# Video_OUT.net
KiCad netlist of a schematic drawn in Altium Designer
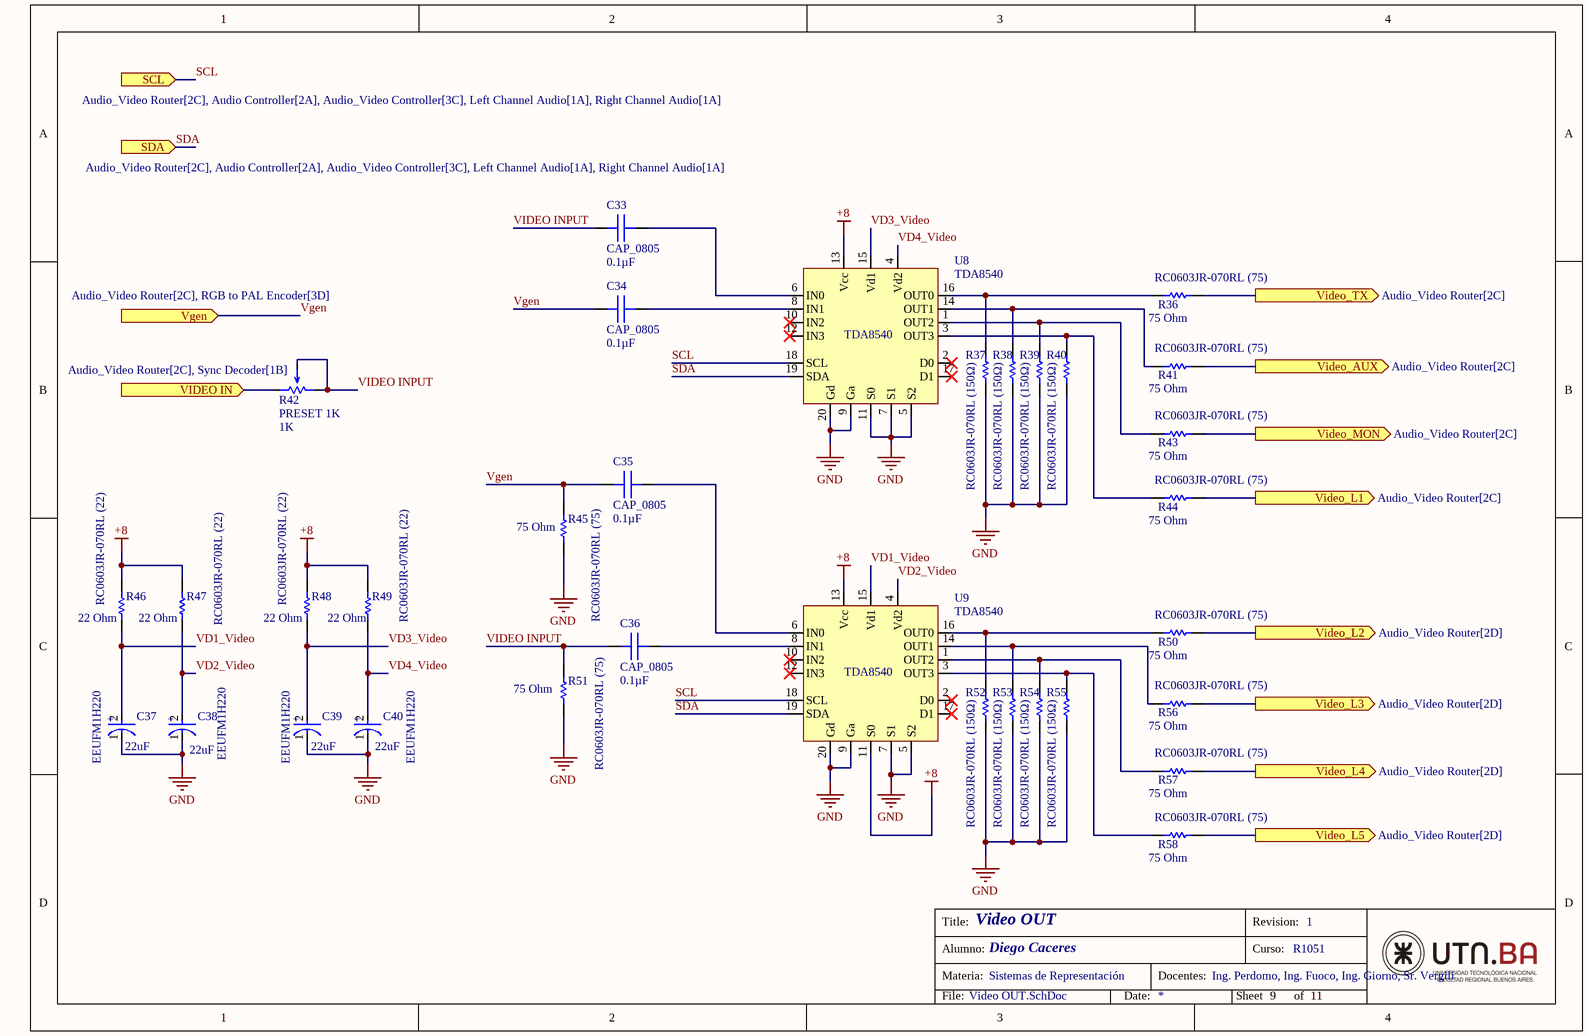
[diagram p0: Video OUT.SchDoc]

(export (version "E")
  (design (tool "Eeschema 10.0.6"))
  (components
    (comp (ref "C33")
      (value "CAP_0805")
      (footprint "0805_CAPACITOR_DCACERES")
      (description "Capacitor SMD, encapsulado 0805")
      (fields (field (name "ALTIUM_VALUE") "0.1µF"))
      (libsource (lib "PF_Schlib") (part "CAPACITOR_0805_Caceres"))
    )
    (comp (ref "C34")
      (value "CAP_0805")
      (footprint "0805_CAPACITOR_DCACERES")
      (description "Capacitor SMD, encapsulado 0805")
      (fields (field (name "ALTIUM_VALUE") "0.1µF"))
      (libsource (lib "PF_Schlib") (part "CAPACITOR_0805_Caceres"))
    )
    (comp (ref "C35")
      (value "CAP_0805")
      (footprint "0805_CAPACITOR_DCACERES")
      (description "Capacitor SMD, encapsulado 0805")
      (fields (field (name "ALTIUM_VALUE") "0.1µF"))
      (libsource (lib "PF_Schlib") (part "CAPACITOR_0805_Caceres"))
    )
    (comp (ref "C36")
      (value "CAP_0805")
      (footprint "0805_CAPACITOR_DCACERES")
      (description "Capacitor SMD, encapsulado 0805")
      (fields (field (name "ALTIUM_VALUE") "0.1µF"))
      (libsource (lib "PF_Schlib") (part "CAPACITOR_0805_Caceres"))
    )
    (comp (ref "C37")
      (value "EEUFM1H220")
      (footprint "FP-RAD-TH-D_5_0_5-L_11_1-MFG")
      (description "Aluminum Electrolytic Capacitors (Radial Lead Type) 22uF ±20% 50V")
      (fields
        (field (name "TOLERANCE") "20%")
        (field (name "VOLTAGE") "50V")
        (field (name "CAPACITANCE") "22uF")
      )
      (libsource (lib "Altium Content Vault") (part "a00bbbee19879c290e62620ae7e47b1"))
    )
    (comp (ref "C38")
      (value "EEUFM1H220")
      (footprint "FP-RAD-TH-D_5_0_5-L_11_1-MFG")
      (description "Aluminum Electrolytic Capacitors (Radial Lead Type) 22uF ±20% 50V")
      (fields
        (field (name "TOLERANCE") "20%")
        (field (name "VOLTAGE") "50V")
        (field (name "CAPACITANCE") "22uF")
      )
      (libsource (lib "Altium Content Vault") (part "a00bbbee19879c290e62620ae7e47b1"))
    )
    (comp (ref "C39")
      (value "EEUFM1H220")
      (footprint "FP-RAD-TH-D_5_0_5-L_11_1-MFG")
      (description "Aluminum Electrolytic Capacitors (Radial Lead Type) 22uF ±20% 50V")
      (fields
        (field (name "TOLERANCE") "20%")
        (field (name "VOLTAGE") "50V")
        (field (name "CAPACITANCE") "22uF")
      )
      (libsource (lib "Altium Content Vault") (part "a00bbbee19879c290e62620ae7e47b1"))
    )
    (comp (ref "C40")
      (value "EEUFM1H220")
      (footprint "FP-RAD-TH-D_5_0_5-L_11_1-MFG")
      (description "Aluminum Electrolytic Capacitors (Radial Lead Type) 22uF ±20% 50V")
      (fields
        (field (name "TOLERANCE") "20%")
        (field (name "VOLTAGE") "50V")
        (field (name "CAPACITANCE") "22uF")
      )
      (libsource (lib "Altium Content Vault") (part "a00bbbee19879c290e62620ae7e47b1"))
    )
    (comp (ref "R36")
      (value "RC0603JR-070RL (75)")
      (footprint "RESC1608X55X25ML10T15")
      (description "Chip Resistor, 0 Ohm, +/- 5%, 0.1 W, -55 to 155 degC, 0603 (1608 Metric), RoHS, Tape and Reel")
      (fields
        (field (name "TOLERANCE") "5%")
        (field (name "RESISTANCE") "75 Ohm")
        (field (name "MANUFACTURER") "Yageo")
      )
      (libsource (lib "Altium Content Vault") (part "RES-2"))
    )
    (comp (ref "R37")
      (value "RC0603JR-070RL (150Ω)")
      (footprint "RESC1608X55X25ML10T15")
      (description "Chip Resistor, 0 Ohm, +/- 5%, 0.1 W, -55 to 155 degC, 0603 (1608 Metric), RoHS, Tape and Reel")
      (fields (field (name "TOLERANCE") "5%") (field (name "MANUFACTURER") "Yageo"))
      (libsource (lib "Altium Content Vault") (part "RES-2"))
    )
    (comp (ref "R38")
      (value "RC0603JR-070RL (150Ω)")
      (footprint "RESC1608X55X25ML10T15")
      (description "Chip Resistor, 0 Ohm, +/- 5%, 0.1 W, -55 to 155 degC, 0603 (1608 Metric), RoHS, Tape and Reel")
      (fields (field (name "TOLERANCE") "5%") (field (name "MANUFACTURER") "Yageo"))
      (libsource (lib "Altium Content Vault") (part "RES-2"))
    )
    (comp (ref "R39")
      (value "RC0603JR-070RL (150Ω)")
      (footprint "RESC1608X55X25ML10T15")
      (description "Chip Resistor, 0 Ohm, +/- 5%, 0.1 W, -55 to 155 degC, 0603 (1608 Metric), RoHS, Tape and Reel")
      (fields (field (name "TOLERANCE") "5%") (field (name "MANUFACTURER") "Yageo"))
      (libsource (lib "Altium Content Vault") (part "RES-2"))
    )
    (comp (ref "R40")
      (value "RC0603JR-070RL (150Ω)")
      (footprint "RESC1608X55X25ML10T15")
      (description "Chip Resistor, 0 Ohm, +/- 5%, 0.1 W, -55 to 155 degC, 0603 (1608 Metric), RoHS, Tape and Reel")
      (fields (field (name "TOLERANCE") "5%") (field (name "MANUFACTURER") "Yageo"))
      (libsource (lib "Altium Content Vault") (part "RES-2"))
    )
    (comp (ref "R41")
      (value "RC0603JR-070RL (75)")
      (footprint "RESC1608X55X25ML10T15")
      (description "Chip Resistor, 0 Ohm, +/- 5%, 0.1 W, -55 to 155 degC, 0603 (1608 Metric), RoHS, Tape and Reel")
      (fields
        (field (name "TOLERANCE") "5%")
        (field (name "RESISTANCE") "75 Ohm")
        (field (name "MANUFACTURER") "Yageo")
      )
      (libsource (lib "Altium Content Vault") (part "RES-2"))
    )
    (comp (ref "R42")
      (value "PRESET 1K")
      (footprint "3386P_PRESET_1K_DCaceres")
      (description "Preset 1k, Thru Hole\r\nManufacturer Part Search 3386P-1-472LF")
      (fields (field (name "ALTIUM_VALUE") "1K") (field (name "PARTNUMBER") "3386P-1-472LF"))
      (libsource (lib "PF_Schlib") (part "Preset_1K_Caceres"))
    )
    (comp (ref "R43")
      (value "RC0603JR-070RL (75)")
      (footprint "RESC1608X55X25ML10T15")
      (description "Chip Resistor, 0 Ohm, +/- 5%, 0.1 W, -55 to 155 degC, 0603 (1608 Metric), RoHS, Tape and Reel")
      (fields
        (field (name "TOLERANCE") "5%")
        (field (name "RESISTANCE") "75 Ohm")
        (field (name "MANUFACTURER") "Yageo")
      )
      (libsource (lib "Altium Content Vault") (part "RES-2"))
    )
    (comp (ref "R44")
      (value "RC0603JR-070RL (75)")
      (footprint "RESC1608X55X25ML10T15")
      (description "Chip Resistor, 0 Ohm, +/- 5%, 0.1 W, -55 to 155 degC, 0603 (1608 Metric), RoHS, Tape and Reel")
      (fields
        (field (name "TOLERANCE") "5%")
        (field (name "RESISTANCE") "75 Ohm")
        (field (name "MANUFACTURER") "Yageo")
      )
      (libsource (lib "Altium Content Vault") (part "RES-2"))
    )
    (comp (ref "R45")
      (value "RC0603JR-070RL (75)")
      (footprint "RESC1608X55X25ML10T15")
      (description "Chip Resistor, 0 Ohm, +/- 5%, 0.1 W, -55 to 155 degC, 0603 (1608 Metric), RoHS, Tape and Reel")
      (fields
        (field (name "TOLERANCE") "5%")
        (field (name "RESISTANCE") "75 Ohm")
        (field (name "MANUFACTURER") "Yageo")
      )
      (libsource (lib "Altium Content Vault") (part "RES-2"))
    )
    (comp (ref "R46")
      (value "RC0603JR-070RL (22)")
      (footprint "RESC1608X55X25ML10T15")
      (description "Chip Resistor, 0 Ohm, +/- 5%, 0.1 W, -55 to 155 degC, 0603 (1608 Metric), RoHS, Tape and Reel")
      (fields
        (field (name "TOLERANCE") "5%")
        (field (name "RESISTANCE") "22 Ohm")
        (field (name "MANUFACTURER") "Yageo")
      )
      (libsource (lib "Altium Content Vault") (part "RES-2"))
    )
    (comp (ref "R47")
      (value "RC0603JR-070RL (22)")
      (footprint "RESC1608X55X25ML10T15")
      (description "Chip Resistor, 0 Ohm, +/- 5%, 0.1 W, -55 to 155 degC, 0603 (1608 Metric), RoHS, Tape and Reel")
      (fields
        (field (name "TOLERANCE") "5%")
        (field (name "RESISTANCE") "22 Ohm")
        (field (name "MANUFACTURER") "Yageo")
      )
      (libsource (lib "Altium Content Vault") (part "RES-2"))
    )
    (comp (ref "R48")
      (value "RC0603JR-070RL (22)")
      (footprint "RESC1608X55X25ML10T15")
      (description "Chip Resistor, 0 Ohm, +/- 5%, 0.1 W, -55 to 155 degC, 0603 (1608 Metric), RoHS, Tape and Reel")
      (fields
        (field (name "TOLERANCE") "5%")
        (field (name "RESISTANCE") "22 Ohm")
        (field (name "MANUFACTURER") "Yageo")
      )
      (libsource (lib "Altium Content Vault") (part "RES-2"))
    )
    (comp (ref "R49")
      (value "RC0603JR-070RL (22)")
      (footprint "RESC1608X55X25ML10T15")
      (description "Chip Resistor, 0 Ohm, +/- 5%, 0.1 W, -55 to 155 degC, 0603 (1608 Metric), RoHS, Tape and Reel")
      (fields
        (field (name "TOLERANCE") "5%")
        (field (name "RESISTANCE") "22 Ohm")
        (field (name "MANUFACTURER") "Yageo")
      )
      (libsource (lib "Altium Content Vault") (part "RES-2"))
    )
    (comp (ref "R50")
      (value "RC0603JR-070RL (75)")
      (footprint "RESC1608X55X25ML10T15")
      (description "Chip Resistor, 0 Ohm, +/- 5%, 0.1 W, -55 to 155 degC, 0603 (1608 Metric), RoHS, Tape and Reel")
      (fields
        (field (name "TOLERANCE") "5%")
        (field (name "RESISTANCE") "75 Ohm")
        (field (name "MANUFACTURER") "Yageo")
      )
      (libsource (lib "Altium Content Vault") (part "RES-2"))
    )
    (comp (ref "R51")
      (value "RC0603JR-070RL (75)")
      (footprint "RESC1608X55X25ML10T15")
      (description "Chip Resistor, 0 Ohm, +/- 5%, 0.1 W, -55 to 155 degC, 0603 (1608 Metric), RoHS, Tape and Reel")
      (fields
        (field (name "TOLERANCE") "5%")
        (field (name "RESISTANCE") "75 Ohm")
        (field (name "MANUFACTURER") "Yageo")
      )
      (libsource (lib "Altium Content Vault") (part "RES-2"))
    )
    (comp (ref "R52")
      (value "RC0603JR-070RL (150Ω)")
      (footprint "RESC1608X55X25ML10T15")
      (description "Chip Resistor, 0 Ohm, +/- 5%, 0.1 W, -55 to 155 degC, 0603 (1608 Metric), RoHS, Tape and Reel")
      (fields (field (name "TOLERANCE") "5%") (field (name "MANUFACTURER") "Yageo"))
      (libsource (lib "Altium Content Vault") (part "RES-2"))
    )
    (comp (ref "R53")
      (value "RC0603JR-070RL (150Ω)")
      (footprint "RESC1608X55X25ML10T15")
      (description "Chip Resistor, 0 Ohm, +/- 5%, 0.1 W, -55 to 155 degC, 0603 (1608 Metric), RoHS, Tape and Reel")
      (fields (field (name "TOLERANCE") "5%") (field (name "MANUFACTURER") "Yageo"))
      (libsource (lib "Altium Content Vault") (part "RES-2"))
    )
    (comp (ref "R54")
      (value "RC0603JR-070RL (150Ω)")
      (footprint "RESC1608X55X25ML10T15")
      (description "Chip Resistor, 0 Ohm, +/- 5%, 0.1 W, -55 to 155 degC, 0603 (1608 Metric), RoHS, Tape and Reel")
      (fields (field (name "TOLERANCE") "5%") (field (name "MANUFACTURER") "Yageo"))
      (libsource (lib "Altium Content Vault") (part "RES-2"))
    )
    (comp (ref "R55")
      (value "RC0603JR-070RL (150Ω)")
      (footprint "RESC1608X55X25ML10T15")
      (description "Chip Resistor, 0 Ohm, +/- 5%, 0.1 W, -55 to 155 degC, 0603 (1608 Metric), RoHS, Tape and Reel")
      (fields (field (name "TOLERANCE") "5%") (field (name "MANUFACTURER") "Yageo"))
      (libsource (lib "Altium Content Vault") (part "RES-2"))
    )
    (comp (ref "R56")
      (value "RC0603JR-070RL (75)")
      (footprint "RESC1608X55X25ML10T15")
      (description "Chip Resistor, 0 Ohm, +/- 5%, 0.1 W, -55 to 155 degC, 0603 (1608 Metric), RoHS, Tape and Reel")
      (fields
        (field (name "TOLERANCE") "5%")
        (field (name "RESISTANCE") "75 Ohm")
        (field (name "MANUFACTURER") "Yageo")
      )
      (libsource (lib "Altium Content Vault") (part "RES-2"))
    )
    (comp (ref "R57")
      (value "RC0603JR-070RL (75)")
      (footprint "RESC1608X55X25ML10T15")
      (description "Chip Resistor, 0 Ohm, +/- 5%, 0.1 W, -55 to 155 degC, 0603 (1608 Metric), RoHS, Tape and Reel")
      (fields
        (field (name "TOLERANCE") "5%")
        (field (name "RESISTANCE") "75 Ohm")
        (field (name "MANUFACTURER") "Yageo")
      )
      (libsource (lib "Altium Content Vault") (part "RES-2"))
    )
    (comp (ref "R58")
      (value "RC0603JR-070RL (75)")
      (footprint "RESC1608X55X25ML10T15")
      (description "Chip Resistor, 0 Ohm, +/- 5%, 0.1 W, -55 to 155 degC, 0603 (1608 Metric), RoHS, Tape and Reel")
      (fields
        (field (name "TOLERANCE") "5%")
        (field (name "RESISTANCE") "75 Ohm")
        (field (name "MANUFACTURER") "Yageo")
      )
      (libsource (lib "Altium Content Vault") (part "RES-2"))
    )
    (comp (ref "U8")
      (value "TDA8540")
      (footprint "SOT146-1_DIP20_TDA8540_DCACERES")
      (description "TDA8540, Thtu Hole\r\nPlastic dual in-line package; 20 leads (300 mil); DIP20; SOT146-1.")
      (libsource (lib "PF_Schlib") (part "TDA8540_Caceres"))
    )
    (comp (ref "U9")
      (value "TDA8540")
      (footprint "SOT146-1_DIP20_TDA8540_DCACERES")
      (description "TDA8540, Thtu Hole\r\nPlastic dual in-line package; 20 leads (300 mil); DIP20; SOT146-1.")
      (libsource (lib "PF_Schlib") (part "TDA8540_Caceres"))
    )
  )
  (nets
    (net (code "1") (name "+8") (class "Default")
      (node (ref "R46") (pin "2") (pinfunction "2_2") (pintype "passive"))
      (node (ref "R47") (pin "2") (pinfunction "2_2") (pintype "passive"))
      (node (ref "R48") (pin "2") (pinfunction "2_2") (pintype "passive"))
      (node (ref "R49") (pin "2") (pinfunction "2_2") (pintype "passive"))
      (node (ref "U8") (pin "13") (pinfunction "Vcc_13") (pintype "passive"))
      (node (ref "U9") (pin "11") (pinfunction "S0_11") (pintype "passive"))
      (node (ref "U9") (pin "13") (pinfunction "Vcc_13") (pintype "passive"))
    )
    (net (code "2") (name "/SCL") (class "Default")
      (node (ref "U8") (pin "18") (pinfunction "SCL_18") (pintype "passive"))
      (node (ref "U9") (pin "18") (pinfunction "SCL_18") (pintype "passive"))
    )
    (net (code "3") (name "/SDA") (class "Default")
      (node (ref "U8") (pin "19") (pinfunction "SDA_19") (pintype "passive"))
      (node (ref "U9") (pin "19") (pinfunction "SDA_19") (pintype "passive"))
    )
    (net (code "4") (name "/VD1_Video") (class "Default")
      (node (ref "C37") (pin "2") (pinfunction "A_2") (pintype "passive"))
      (node (ref "R46") (pin "1") (pinfunction "1_1") (pintype "passive"))
      (node (ref "U9") (pin "15") (pinfunction "Vd1_15") (pintype "passive"))
    )
    (net (code "5") (name "/VD2_Video") (class "Default")
      (node (ref "C38") (pin "2") (pinfunction "A_2") (pintype "passive"))
      (node (ref "R47") (pin "1") (pinfunction "1_1") (pintype "passive"))
      (node (ref "U9") (pin "4") (pinfunction "Vd2_4") (pintype "passive"))
    )
    (net (code "6") (name "/VD3_Video") (class "Default")
      (node (ref "C39") (pin "2") (pinfunction "A_2") (pintype "passive"))
      (node (ref "R48") (pin "1") (pinfunction "1_1") (pintype "passive"))
      (node (ref "U8") (pin "15") (pinfunction "Vd1_15") (pintype "passive"))
    )
    (net (code "7") (name "/VD4_Video") (class "Default")
      (node (ref "C40") (pin "2") (pinfunction "A_2") (pintype "passive"))
      (node (ref "R49") (pin "1") (pinfunction "1_1") (pintype "passive"))
      (node (ref "U8") (pin "4") (pinfunction "Vd2_4") (pintype "passive"))
    )
    (net (code "8") (name "/VIDEO IN") (class "Default")
      (node (ref "R42") (pin "2") (pinfunction "1_2") (pintype "passive"))
    )
    (net (code "9") (name "/VIDEO INPUT") (class "Default")
      (node (ref "C33") (pin "1") (pinfunction "1_1") (pintype "passive"))
      (node (ref "C36") (pin "1") (pinfunction "1_1") (pintype "passive"))
      (node (ref "R42") (pin "1") (pinfunction "1_1") (pintype "passive"))
      (node (ref "R42") (pin "3") (pinfunction "3_3") (pintype "passive"))
      (node (ref "R51") (pin "2") (pinfunction "2_2") (pintype "passive"))
    )
    (net (code "10") (name "/Vgen") (class "Default")
      (node (ref "C34") (pin "1") (pinfunction "1_1") (pintype "passive"))
      (node (ref "C35") (pin "1") (pinfunction "1_1") (pintype "passive"))
      (node (ref "R45") (pin "2") (pinfunction "2_2") (pintype "passive"))
    )
    (net (code "11") (name "/Video_AUX") (class "Default")
      (node (ref "R41") (pin "2") (pinfunction "2_2") (pintype "passive"))
    )
    (net (code "12") (name "/Video_L1") (class "Default")
      (node (ref "R44") (pin "2") (pinfunction "2_2") (pintype "passive"))
    )
    (net (code "13") (name "/Video_L2") (class "Default")
      (node (ref "R50") (pin "2") (pinfunction "2_2") (pintype "passive"))
    )
    (net (code "14") (name "/Video_L3") (class "Default")
      (node (ref "R56") (pin "2") (pinfunction "2_2") (pintype "passive"))
    )
    (net (code "15") (name "/Video_L4") (class "Default")
      (node (ref "R57") (pin "2") (pinfunction "2_2") (pintype "passive"))
    )
    (net (code "16") (name "/Video_L5") (class "Default")
      (node (ref "R58") (pin "2") (pinfunction "2_2") (pintype "passive"))
    )
    (net (code "17") (name "/Video_MON") (class "Default")
      (node (ref "R43") (pin "2") (pinfunction "2_2") (pintype "passive"))
    )
    (net (code "18") (name "/Video_TX") (class "Default")
      (node (ref "R36") (pin "2") (pinfunction "2_2") (pintype "passive"))
    )
    (net (code "19") (name "GND") (class "Default")
      (node (ref "C37") (pin "1") (pinfunction "C_1") (pintype "passive"))
      (node (ref "C38") (pin "1") (pinfunction "C_1") (pintype "passive"))
      (node (ref "C39") (pin "1") (pinfunction "C_1") (pintype "passive"))
      (node (ref "C40") (pin "1") (pinfunction "C_1") (pintype "passive"))
      (node (ref "R37") (pin "2") (pinfunction "2_2") (pintype "passive"))
      (node (ref "R38") (pin "2") (pinfunction "2_2") (pintype "passive"))
      (node (ref "R39") (pin "2") (pinfunction "2_2") (pintype "passive"))
      (node (ref "R40") (pin "2") (pinfunction "2_2") (pintype "passive"))
      (node (ref "R45") (pin "1") (pinfunction "1_1") (pintype "passive"))
      (node (ref "R51") (pin "1") (pinfunction "1_1") (pintype "passive"))
      (node (ref "R52") (pin "2") (pinfunction "2_2") (pintype "passive"))
      (node (ref "R53") (pin "2") (pinfunction "2_2") (pintype "passive"))
      (node (ref "R54") (pin "2") (pinfunction "2_2") (pintype "passive"))
      (node (ref "R55") (pin "2") (pinfunction "2_2") (pintype "passive"))
      (node (ref "U8") (pin "11") (pinfunction "S0_11") (pintype "passive"))
      (node (ref "U8") (pin "20") (pinfunction "Gd_20") (pintype "passive"))
      (node (ref "U8") (pin "5") (pinfunction "S2_5") (pintype "passive"))
      (node (ref "U8") (pin "7") (pinfunction "S1_7") (pintype "passive"))
      (node (ref "U8") (pin "9") (pinfunction "Ga_9") (pintype "passive"))
      (node (ref "U9") (pin "20") (pinfunction "Gd_20") (pintype "passive"))
      (node (ref "U9") (pin "5") (pinfunction "S2_5") (pintype "passive"))
      (node (ref "U9") (pin "7") (pinfunction "S1_7") (pintype "passive"))
      (node (ref "U9") (pin "9") (pinfunction "Ga_9") (pintype "passive"))
    )
    (net (code "20") (name "Net-(U8-IN0)") (class "Default")
      (node (ref "C33") (pin "2") (pinfunction "2_2") (pintype "passive"))
      (node (ref "U8") (pin "6") (pinfunction "IN0_6") (pintype "passive"))
    )
    (net (code "21") (name "Net-(U8-IN1)") (class "Default")
      (node (ref "C34") (pin "2") (pinfunction "2_2") (pintype "passive"))
      (node (ref "U8") (pin "8") (pinfunction "IN1_8") (pintype "passive"))
    )
    (net (code "22") (name "Net-(U8-OUT0)") (class "Default")
      (node (ref "R36") (pin "1") (pinfunction "1_1") (pintype "passive"))
      (node (ref "R37") (pin "1") (pinfunction "1_1") (pintype "passive"))
      (node (ref "U8") (pin "16") (pinfunction "OUT0_16") (pintype "passive"))
    )
    (net (code "23") (name "Net-(U8-OUT1)") (class "Default")
      (node (ref "R38") (pin "1") (pinfunction "1_1") (pintype "passive"))
      (node (ref "R41") (pin "1") (pinfunction "1_1") (pintype "passive"))
      (node (ref "U8") (pin "14") (pinfunction "OUT1_14") (pintype "passive"))
    )
    (net (code "24") (name "Net-(U8-OUT2)") (class "Default")
      (node (ref "R39") (pin "1") (pinfunction "1_1") (pintype "passive"))
      (node (ref "R43") (pin "1") (pinfunction "1_1") (pintype "passive"))
      (node (ref "U8") (pin "1") (pinfunction "OUT2_1") (pintype "passive"))
    )
    (net (code "25") (name "Net-(U8-OUT3)") (class "Default")
      (node (ref "R40") (pin "1") (pinfunction "1_1") (pintype "passive"))
      (node (ref "R44") (pin "1") (pinfunction "1_1") (pintype "passive"))
      (node (ref "U8") (pin "3") (pinfunction "OUT3_3") (pintype "passive"))
    )
    (net (code "26") (name "Net-(U9-IN0)") (class "Default")
      (node (ref "C35") (pin "2") (pinfunction "2_2") (pintype "passive"))
      (node (ref "U9") (pin "6") (pinfunction "IN0_6") (pintype "passive"))
    )
    (net (code "27") (name "Net-(U9-IN1)") (class "Default")
      (node (ref "C36") (pin "2") (pinfunction "2_2") (pintype "passive"))
      (node (ref "U9") (pin "8") (pinfunction "IN1_8") (pintype "passive"))
    )
    (net (code "28") (name "Net-(U9-OUT0)") (class "Default")
      (node (ref "R50") (pin "1") (pinfunction "1_1") (pintype "passive"))
      (node (ref "R52") (pin "1") (pinfunction "1_1") (pintype "passive"))
      (node (ref "U9") (pin "16") (pinfunction "OUT0_16") (pintype "passive"))
    )
    (net (code "29") (name "Net-(U9-OUT1)") (class "Default")
      (node (ref "R53") (pin "1") (pinfunction "1_1") (pintype "passive"))
      (node (ref "R56") (pin "1") (pinfunction "1_1") (pintype "passive"))
      (node (ref "U9") (pin "14") (pinfunction "OUT1_14") (pintype "passive"))
    )
    (net (code "30") (name "Net-(U9-OUT2)") (class "Default")
      (node (ref "R54") (pin "1") (pinfunction "1_1") (pintype "passive"))
      (node (ref "R57") (pin "1") (pinfunction "1_1") (pintype "passive"))
      (node (ref "U9") (pin "1") (pinfunction "OUT2_1") (pintype "passive"))
    )
    (net (code "31") (name "Net-(U9-OUT3)") (class "Default")
      (node (ref "R55") (pin "1") (pinfunction "1_1") (pintype "passive"))
      (node (ref "R58") (pin "1") (pinfunction "1_1") (pintype "passive"))
      (node (ref "U9") (pin "3") (pinfunction "OUT3_3") (pintype "passive"))
    )
    (net (code "32") (name "unconnected-(U8-D0-Pad2)") (class "Default")
      (node (ref "U8") (pin "2") (pinfunction "D0_2") (pintype "passive+no_connect"))
    )
    (net (code "33") (name "unconnected-(U8-D1-Pad17)") (class "Default")
      (node (ref "U8") (pin "17") (pinfunction "D1_17") (pintype "passive+no_connect"))
    )
    (net (code "34") (name "unconnected-(U8-IN2-Pad10)") (class "Default")
      (node (ref "U8") (pin "10") (pinfunction "IN2_10") (pintype "passive+no_connect"))
    )
    (net (code "35") (name "unconnected-(U8-IN3-Pad12)") (class "Default")
      (node (ref "U8") (pin "12") (pinfunction "IN3_12") (pintype "passive+no_connect"))
    )
    (net (code "36") (name "unconnected-(U9-D0-Pad2)") (class "Default")
      (node (ref "U9") (pin "2") (pinfunction "D0_2") (pintype "passive+no_connect"))
    )
    (net (code "37") (name "unconnected-(U9-D1-Pad17)") (class "Default")
      (node (ref "U9") (pin "17") (pinfunction "D1_17") (pintype "passive+no_connect"))
    )
    (net (code "38") (name "unconnected-(U9-IN2-Pad10)") (class "Default")
      (node (ref "U9") (pin "10") (pinfunction "IN2_10") (pintype "passive+no_connect"))
    )
    (net (code "39") (name "unconnected-(U9-IN3-Pad12)") (class "Default")
      (node (ref "U9") (pin "12") (pinfunction "IN3_12") (pintype "passive+no_connect"))
    )
  )
)
